# electromagnet_crane_toy_schematics.net
KiCad netlist of a schematic drawn in EAGLE
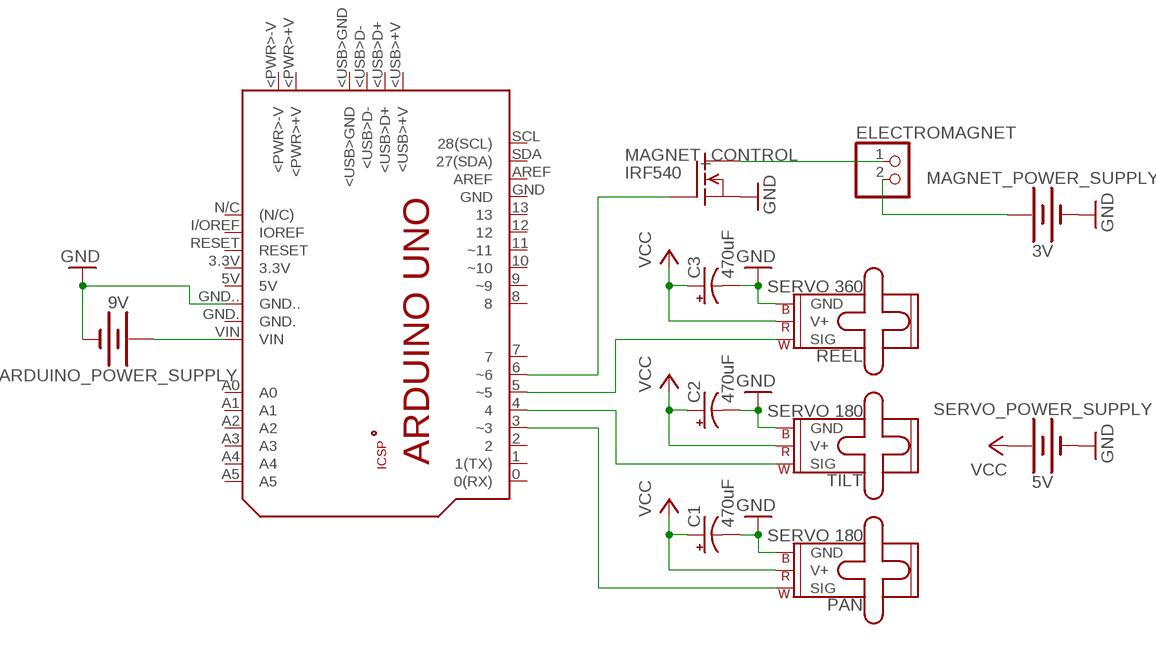
[diagram p0: schematic, sheet 1]

(export (version "E")
  (design (tool "Eeschema 10.0.6"))
  (components
    (comp (ref "ARDUINO_POWER_SUPPLY")
      (value "9V")
      (footprint "eagle-import:BATTCON_9V")
      (libsource (lib "eagle-import") (part "BATTERY-9V"))
    )
    (comp (ref "C1")
      (value "470uF")
      (footprint "eagle-import:153CLV-1014")
      (libsource (lib "eagle-import") (part "CPOL-US153CLV-1014"))
    )
    (comp (ref "C2")
      (value "470uF")
      (footprint "eagle-import:153CLV-1014")
      (libsource (lib "eagle-import") (part "CPOL-US153CLV-1014"))
    )
    (comp (ref "C3")
      (value "470uF")
      (footprint "eagle-import:153CLV-1014")
      (libsource (lib "eagle-import") (part "CPOL-US153CLV-1014"))
    )
    (comp (ref "ELECTROMAGNET")
      (value "PINHD-1X2")
      (footprint "eagle-import:1X02")
      (libsource (lib "eagle-import") (part "PINHD-1X2"))
    )
    (comp (ref "MAGNET_CONTROL")
      (value "IRF540")
      (footprint "eagle-import:TO220")
      (libsource (lib "eagle-import") (part "IRF540"))
    )
    (comp (ref "MAGNET_POWER_SUPPLY")
      (value "3V")
      (footprint "eagle-import:BATTERY-AA-KIT")
      (libsource (lib "eagle-import") (part "BATTERY-AA_KIT"))
    )
    (comp (ref "PAN")
      (value "SERVO 180")
      (footprint "eagle-import:1X03")
      (libsource (lib "eagle-import") (part "SERVO"))
    )
    (comp (ref "PCB1")
      (value "ARDUINO_UNO")
      (footprint "eagle-import:ARDUINO_UNO")
      (libsource (lib "eagle-import") (part "ARDUINO_UNO"))
    )
    (comp (ref "REEL")
      (value "SERVO 360")
      (footprint "eagle-import:1X03")
      (libsource (lib "eagle-import") (part "SERVO"))
    )
    (comp (ref "SERVO_POWER_SUPPLY")
      (value "5V")
      (footprint "eagle-import:BATTERY-AA-KIT")
      (libsource (lib "eagle-import") (part "BATTERY-AA_KIT"))
    )
    (comp (ref "TILT")
      (value "SERVO 180")
      (footprint "eagle-import:1X03")
      (libsource (lib "eagle-import") (part "SERVO"))
    )
  )
  (nets
    (net (code "1") (name "GND") (class "Default")
      (node (ref "ARDUINO_POWER_SUPPLY") (pin "-") (pinfunction "-_-") (pintype "power_in"))
      (node (ref "C1") (pin "-") (pinfunction "-_-") (pintype "passive"))
      (node (ref "C2") (pin "-") (pinfunction "-_-") (pintype "passive"))
      (node (ref "C3") (pin "-") (pinfunction "-_-") (pintype "passive"))
      (node (ref "MAGNET_CONTROL") (pin "3") (pinfunction "S_3") (pintype "passive"))
      (node (ref "MAGNET_POWER_SUPPLY") (pin "GND@1") (pinfunction "-_GND@1") (pintype "power_in"))
      (node (ref "PAN") (pin "3") (pinfunction "GND_3") (pintype "bidirectional"))
      (node (ref "PCB1") (pin "GND..") (pinfunction "GND.._GND..") (pintype "bidirectional"))
      (node (ref "REEL") (pin "3") (pinfunction "GND_3") (pintype "bidirectional"))
      (node (ref "SERVO_POWER_SUPPLY") (pin "GND@1") (pinfunction "-_GND@1") (pintype "power_in"))
      (node (ref "TILT") (pin "3") (pinfunction "GND_3") (pintype "bidirectional"))
    )
    (net (code "2") (name "Net-(ARDUINO_POWER_SUPPLY-Pad+)") (class "Default")
      (node (ref "ARDUINO_POWER_SUPPLY") (pin "+") (pinfunction "+_+") (pintype "power_in"))
      (node (ref "PCB1") (pin "VIN") (pinfunction "VIN_VIN") (pintype "bidirectional"))
    )
    (net (code "3") (name "Net-(MAGNET_CONTROL-D)") (class "Default")
      (node (ref "ELECTROMAGNET") (pin "1") (pinfunction "1_1") (pintype "passive"))
      (node (ref "MAGNET_CONTROL") (pin "2") (pinfunction "D_2") (pintype "passive"))
    )
    (net (code "4") (name "Net-(MAGNET_CONTROL-G)") (class "Default")
      (node (ref "MAGNET_CONTROL") (pin "1") (pinfunction "G_1") (pintype "passive"))
      (node (ref "PCB1") (pin "6") (pinfunction "~{6}_6") (pintype "bidirectional"))
    )
    (net (code "5") (name "Net-(MAGNET_POWER_SUPPLY-+)") (class "Default")
      (node (ref "ELECTROMAGNET") (pin "2") (pinfunction "2_2") (pintype "passive"))
      (node (ref "MAGNET_POWER_SUPPLY") (pin "PWR@1") (pinfunction "+_PWR@1") (pintype "power_in"))
    )
    (net (code "6") (name "Net-(PAN-SIG)") (class "Default")
      (node (ref "PAN") (pin "1") (pinfunction "SIG_1") (pintype "bidirectional"))
      (node (ref "PCB1") (pin "3") (pinfunction "~{3}_3") (pintype "bidirectional"))
    )
    (net (code "7") (name "Net-(PCB1-~{5})") (class "Default")
      (node (ref "PCB1") (pin "5") (pinfunction "~{5}_5") (pintype "bidirectional"))
      (node (ref "REEL") (pin "1") (pinfunction "SIG_1") (pintype "bidirectional"))
    )
    (net (code "8") (name "Net-(TILT-SIG)") (class "Default")
      (node (ref "PCB1") (pin "4") (pinfunction "4_4") (pintype "bidirectional"))
      (node (ref "TILT") (pin "1") (pinfunction "SIG_1") (pintype "bidirectional"))
    )
    (net (code "9") (name "VCC") (class "Default")
      (node (ref "C1") (pin "+") (pinfunction "+_+") (pintype "passive"))
      (node (ref "C2") (pin "+") (pinfunction "+_+") (pintype "passive"))
      (node (ref "C3") (pin "+") (pinfunction "+_+") (pintype "passive"))
      (node (ref "PAN") (pin "2") (pinfunction "V+_2") (pintype "bidirectional"))
      (node (ref "REEL") (pin "2") (pinfunction "V+_2") (pintype "bidirectional"))
      (node (ref "SERVO_POWER_SUPPLY") (pin "PWR@1") (pinfunction "+_PWR@1") (pintype "power_in"))
      (node (ref "TILT") (pin "2") (pinfunction "V+_2") (pintype "bidirectional"))
    )
    (net (code "10") (name "unconnected-(PCB1-(N{slash}C)-PadN{slash}C)") (class "Default")
      (node (ref "PCB1") (pin "N/C") (pinfunction "(N/C)_N/C") (pintype "bidirectional"))
    )
    (net (code "11") (name "unconnected-(PCB1-0(RX)-Pad0)") (class "Default")
      (node (ref "PCB1") (pin "0") (pinfunction "0(RX)_0") (pintype "bidirectional"))
    )
    (net (code "12") (name "unconnected-(PCB1-1(TX)-Pad1)") (class "Default")
      (node (ref "PCB1") (pin "1") (pinfunction "1(TX)_1") (pintype "bidirectional"))
    )
    (net (code "13") (name "unconnected-(PCB1-27(SDA)-PadSDA)") (class "Default")
      (node (ref "PCB1") (pin "SDA") (pinfunction "27(SDA)_SDA") (pintype "bidirectional"))
    )
    (net (code "14") (name "unconnected-(PCB1-28(SCL)-PadSCL)") (class "Default")
      (node (ref "PCB1") (pin "SCL") (pinfunction "28(SCL)_SCL") (pintype "bidirectional"))
    )
    (net (code "15") (name "unconnected-(PCB1-IOREF-PadI{slash}OREF)") (class "Default")
      (node (ref "PCB1") (pin "I/OREF") (pinfunction "IOREF_I/OREF") (pintype "bidirectional"))
    )
    (net (code "16") (name "unconnected-(PCB1-Pad+5V)") (class "Default")
      (node (ref "PCB1") (pin "+5V") (pinfunction "+5V_+5V") (pintype "bidirectional"))
    )
    (net (code "17") (name "unconnected-(PCB1-Pad2)") (class "Default")
      (node (ref "PCB1") (pin "2") (pinfunction "2_2") (pintype "bidirectional"))
    )
    (net (code "18") (name "unconnected-(PCB1-Pad3.3V)") (class "Default")
      (node (ref "PCB1") (pin "3.3V") (pinfunction "3.3V_3.3V") (pintype "bidirectional"))
    )
    (net (code "19") (name "unconnected-(PCB1-Pad5V)") (class "Default")
      (node (ref "PCB1") (pin "5V") (pinfunction "5V_5V") (pintype "bidirectional"))
    )
    (net (code "20") (name "unconnected-(PCB1-Pad7)") (class "Default")
      (node (ref "PCB1") (pin "7") (pinfunction "7_7") (pintype "bidirectional"))
    )
    (net (code "21") (name "unconnected-(PCB1-Pad8)") (class "Default")
      (node (ref "PCB1") (pin "8") (pinfunction "8_8") (pintype "bidirectional"))
    )
    (net (code "22") (name "unconnected-(PCB1-Pad12)") (class "Default")
      (node (ref "PCB1") (pin "12") (pinfunction "12_12") (pintype "bidirectional"))
    )
    (net (code "23") (name "unconnected-(PCB1-Pad13)") (class "Default")
      (node (ref "PCB1") (pin "13") (pinfunction "13_13") (pintype "bidirectional"))
    )
    (net (code "24") (name "unconnected-(PCB1-Pad<PWR>+V)") (class "Default")
      (node (ref "PCB1") (pin "<PWR>+V") (pinfunction "<PWR>+V_<PWR>+V") (pintype "bidirectional"))
    )
    (net (code "25") (name "unconnected-(PCB1-Pad<PWR>-V)") (class "Default")
      (node (ref "PCB1") (pin "<PWR>-V") (pinfunction "<PWR>-V_<PWR>-V") (pintype "bidirectional"))
    )
    (net (code "26") (name "unconnected-(PCB1-Pad<USB>+V)") (class "Default")
      (node (ref "PCB1") (pin "<USB>+V") (pinfunction "<USB>+V_<USB>+V") (pintype "bidirectional"))
    )
    (net (code "27") (name "unconnected-(PCB1-Pad<USB>D+)") (class "Default")
      (node (ref "PCB1") (pin "<USB>D+") (pinfunction "<USB>D+_<USB>D+") (pintype "bidirectional"))
    )
    (net (code "28") (name "unconnected-(PCB1-Pad<USB>D-)") (class "Default")
      (node (ref "PCB1") (pin "<USB>D-") (pinfunction "<USB>D-_<USB>D-") (pintype "bidirectional"))
    )
    (net (code "29") (name "unconnected-(PCB1-Pad<USB>GND)") (class "Default")
      (node (ref "PCB1") (pin "<USB>GND") (pinfunction "<USB>GND_<USB>GND") (pintype "bidirectional"))
    )
    (net (code "30") (name "unconnected-(PCB1-PadA0)") (class "Default")
      (node (ref "PCB1") (pin "A0") (pinfunction "A0_A0") (pintype "bidirectional"))
    )
    (net (code "31") (name "unconnected-(PCB1-PadA1)") (class "Default")
      (node (ref "PCB1") (pin "A1") (pinfunction "A1_A1") (pintype "bidirectional"))
    )
    (net (code "32") (name "unconnected-(PCB1-PadA2)") (class "Default")
      (node (ref "PCB1") (pin "A2") (pinfunction "A2_A2") (pintype "bidirectional"))
    )
    (net (code "33") (name "unconnected-(PCB1-PadA3)") (class "Default")
      (node (ref "PCB1") (pin "A3") (pinfunction "A3_A3") (pintype "bidirectional"))
    )
    (net (code "34") (name "unconnected-(PCB1-PadA4)") (class "Default")
      (node (ref "PCB1") (pin "A4") (pinfunction "A4_A4") (pintype "bidirectional"))
    )
    (net (code "35") (name "unconnected-(PCB1-PadA5)") (class "Default")
      (node (ref "PCB1") (pin "A5") (pinfunction "A5_A5") (pintype "bidirectional"))
    )
    (net (code "36") (name "unconnected-(PCB1-PadAREF)") (class "Default")
      (node (ref "PCB1") (pin "AREF") (pinfunction "AREF_AREF") (pintype "bidirectional"))
    )
    (net (code "37") (name "unconnected-(PCB1-PadGND)") (class "Default")
      (node (ref "PCB1") (pin "GND") (pinfunction "GND_GND") (pintype "bidirectional"))
    )
    (net (code "38") (name "unconnected-(PCB1-PadGND.)") (class "Default")
      (node (ref "PCB1") (pin "GND.") (pinfunction "GND._GND.") (pintype "bidirectional"))
    )
    (net (code "39") (name "unconnected-(PCB1-PadGND_)") (class "Default")
      (node (ref "PCB1") (pin "GND_") (pinfunction "GND__GND_") (pintype "bidirectional"))
    )
    (net (code "40") (name "unconnected-(PCB1-PadMISO)") (class "Default")
      (node (ref "PCB1") (pin "MISO") (pinfunction "MISO_MISO") (pintype "bidirectional"))
    )
    (net (code "41") (name "unconnected-(PCB1-PadMOSI)") (class "Default")
      (node (ref "PCB1") (pin "MOSI") (pinfunction "MOSI_MOSI") (pintype "bidirectional"))
    )
    (net (code "42") (name "unconnected-(PCB1-PadRESET)") (class "Default")
      (node (ref "PCB1") (pin "RESET") (pinfunction "RESET_RESET") (pintype "bidirectional"))
    )
    (net (code "43") (name "unconnected-(PCB1-PadRESET.)") (class "Default")
      (node (ref "PCB1") (pin "RESET.") (pinfunction "RESET._RESET.") (pintype "bidirectional"))
    )
    (net (code "44") (name "unconnected-(PCB1-PadSCK)") (class "Default")
      (node (ref "PCB1") (pin "SCK") (pinfunction "SCK_SCK") (pintype "bidirectional"))
    )
    (net (code "45") (name "unconnected-(PCB1-~{9}-Pad9)") (class "Default")
      (node (ref "PCB1") (pin "9") (pinfunction "~{9}_9") (pintype "bidirectional"))
    )
    (net (code "46") (name "unconnected-(PCB1-~{10}-Pad10)") (class "Default")
      (node (ref "PCB1") (pin "10") (pinfunction "~{10}_10") (pintype "bidirectional"))
    )
    (net (code "47") (name "unconnected-(PCB1-~{11}-Pad11)") (class "Default")
      (node (ref "PCB1") (pin "11") (pinfunction "~{11}_11") (pintype "bidirectional"))
    )
  )
)
